# USB_CAN.net
KiCad netlist of a schematic drawn in Altium Designer
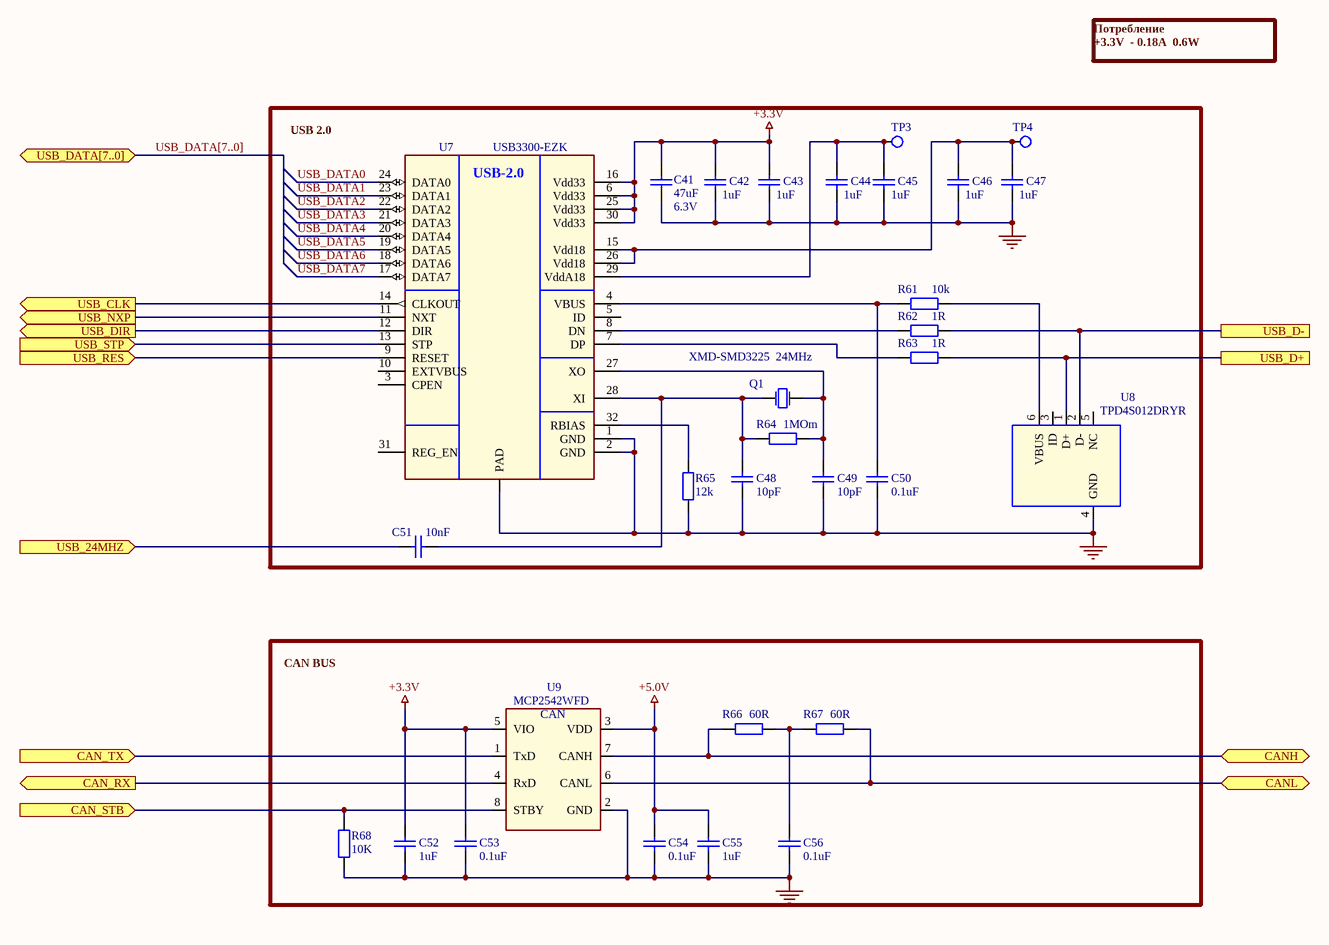
[diagram p0: USB_CAN.SchDoc]

(export (version "E")
  (design (tool "Eeschema 10.0.6"))
  (components
    (comp (ref "C41")
      (value "47uF")
      (footprint "C0805")
      (description "C0805C476M9PAC")
      (fields (field (name "VOLTAGE") "6.3V") (field (name "Comment") "Cap"))
      (libsource (lib "Terra") (part "Cap"))
    )
    (comp (ref "C42")
      (value "1uF")
      (footprint "C0603")
      (description "Конденсатор керамический")
      (fields (field (name "Comment") "Cap"))
      (libsource (lib "Terra") (part "Cap"))
    )
    (comp (ref "C43")
      (value "1uF")
      (footprint "C0603")
      (description "Конденсатор керамический")
      (fields (field (name "Comment") "Cap"))
      (libsource (lib "Terra") (part "Cap"))
    )
    (comp (ref "C44")
      (value "1uF")
      (footprint "C0603")
      (description "Конденсатор керамический")
      (fields (field (name "Comment") "Cap"))
      (libsource (lib "Terra") (part "Cap"))
    )
    (comp (ref "C45")
      (value "1uF")
      (footprint "C0603")
      (description "Конденсатор керамический")
      (fields (field (name "Comment") "Cap"))
      (libsource (lib "Terra") (part "Cap"))
    )
    (comp (ref "C46")
      (value "1uF")
      (footprint "C0603")
      (description "Конденсатор керамический")
      (fields (field (name "Comment") "Cap"))
      (libsource (lib "Terra") (part "Cap"))
    )
    (comp (ref "C47")
      (value "1uF")
      (footprint "C0603")
      (description "Конденсатор керамический")
      (fields (field (name "Comment") "Cap"))
      (libsource (lib "Terra") (part "Cap"))
    )
    (comp (ref "C48")
      (value "10pF")
      (footprint "C0402")
      (description "GRM1535C1H100J")
      (fields (field (name "Comment") "Cap"))
      (libsource (lib "Terra") (part "Cap"))
    )
    (comp (ref "C49")
      (value "10pF")
      (footprint "C0402")
      (description "GRM1535C1H100J")
      (fields (field (name "Comment") "Cap"))
      (libsource (lib "Terra") (part "Cap"))
    )
    (comp (ref "C50")
      (value "0.1uF")
      (footprint "C0402")
      (description "Конденсатор керамический")
      (fields (field (name "VOLTAGE") "25V") (field (name "Comment") "Cap"))
      (libsource (lib "Terra") (part "Cap"))
    )
    (comp (ref "C51")
      (value "10nF")
      (footprint "C0402")
      (description "Конденсатор керамический")
      (fields (field (name "VOLTAGE") "25V") (field (name "Comment") "Cap"))
      (libsource (lib "Terra") (part "Cap"))
    )
    (comp (ref "C52")
      (value "1uF")
      (footprint "C0603")
      (description "Конденсатор керамический")
      (fields (field (name "Comment") "Cap"))
      (libsource (lib "Terra") (part "Cap"))
    )
    (comp (ref "C53")
      (value "0.1uF")
      (footprint "C0402")
      (description "Конденсатор керамический")
      (fields (field (name "VOLTAGE") "25V") (field (name "Comment") "Cap"))
      (libsource (lib "Terra") (part "Cap"))
    )
    (comp (ref "C54")
      (value "0.1uF")
      (footprint "C0402")
      (description "Конденсатор керамический")
      (fields (field (name "VOLTAGE") "25V") (field (name "Comment") "Cap"))
      (libsource (lib "Terra") (part "Cap"))
    )
    (comp (ref "C55")
      (value "1uF")
      (footprint "C0603")
      (description "Конденсатор керамический")
      (fields (field (name "Comment") "Cap"))
      (libsource (lib "Terra") (part "Cap"))
    )
    (comp (ref "C56")
      (value "0.1uF")
      (footprint "C0402")
      (description "Конденсатор керамический")
      (fields (field (name "VOLTAGE") "25V") (field (name "Comment") "Cap"))
      (libsource (lib "Terra") (part "Cap"))
    )
    (comp (ref "Q1")
      (value "XMD-SMD3225  24MHz")
      (footprint "KX-5T")
      (description "Chengdu Kingbri Frequency Technology Co., Ltd   24MHz")
      (libsource (lib "common") (part "XTAL"))
    )
    (comp (ref "R61")
      (value "10k")
      (footprint "R0402")
      (description "Резистор")
      (fields (field (name "Comment") "Res2"))
      (libsource (lib "") (part "Res2_2"))
    )
    (comp (ref "R62")
      (value "1R")
      (footprint "R0402")
      (description "Резистор")
      (fields (field (name "Comment") "Res2"))
      (libsource (lib "Terra") (part "Res2"))
    )
    (comp (ref "R63")
      (value "1R")
      (footprint "R0402")
      (description "Резистор")
      (fields (field (name "Comment") "Res2"))
      (libsource (lib "Terra") (part "Res2"))
    )
    (comp (ref "R64")
      (value "1MOm")
      (footprint "R0402")
      (description "Резистор")
      (fields (field (name "Comment") "Res2"))
      (libsource (lib "") (part "Res2_2"))
    )
    (comp (ref "R65")
      (value "12k")
      (footprint "R0402")
      (description "Резистор")
      (fields (field (name "Comment") "Res2"))
      (libsource (lib "") (part "Res2_1"))
    )
    (comp (ref "R66")
      (value "60R")
      (footprint "R0402")
      (description "Резистор")
      (fields (field (name "Comment") "Res2"))
      (libsource (lib "Terra") (part "Res2"))
    )
    (comp (ref "R67")
      (value "60R")
      (footprint "R0402")
      (description "Резистор")
      (fields (field (name "Comment") "Res2"))
      (libsource (lib "Terra") (part "Res2"))
    )
    (comp (ref "R68")
      (value "10K")
      (footprint "R0402")
      (description "Резистор")
      (fields (field (name "Comment") "Res2"))
      (libsource (lib "") (part "Res2_1"))
    )
    (comp (ref "TP3")
      (value "~")
      (footprint "TP_0MM5_1MM0")
      (description "Тестовая точка на плате")
      (libsource (lib "*") (part "Test_Point"))
    )
    (comp (ref "TP4")
      (value "~")
      (footprint "TP_0MM5_1MM0")
      (description "Тестовая точка на плате")
      (libsource (lib "*") (part "Test_Point"))
    )
    (comp (ref "U7")
      (value "USB3300-EZK")
      (footprint "QFN-32")
      (description "USB-2.0 driver")
      (libsource (lib "Terra") (part "USB3300"))
    )
    (comp (ref "U8")
      (value "TPD4S012DRYR")
      (footprint "TPD4S012DRYR")
      (description "Защитные диоды USB")
      (libsource (lib "common") (part "TPD4S012DRYR"))
    )
    (comp (ref "U9")
      (value "MCP2542WFD")
      (footprint "SO8")
      (description "CAN Transceiver")
      (libsource (lib "common") (part "MCP2542"))
    )
  )
  (nets
    (net (code "1") (name "+3.3V") (class "Default")
      (node (ref "C41") (pin "1") (pinfunction "1_1") (pintype "passive"))
      (node (ref "C42") (pin "2") (pinfunction "2_2") (pintype "passive"))
      (node (ref "C43") (pin "2") (pinfunction "2_2") (pintype "passive"))
      (node (ref "C52") (pin "1") (pinfunction "1_1") (pintype "passive"))
      (node (ref "C53") (pin "1") (pinfunction "1_1") (pintype "passive"))
      (node (ref "U7") (pin "16") (pinfunction "Vdd33_16") (pintype "power_in"))
      (node (ref "U7") (pin "25") (pinfunction "Vdd33_25") (pintype "power_in"))
      (node (ref "U7") (pin "30") (pinfunction "Vdd33_30") (pintype "power_in"))
      (node (ref "U7") (pin "6") (pinfunction "Vdd33_6") (pintype "power_in"))
      (node (ref "U9") (pin "5") (pinfunction "VIO_5") (pintype "passive"))
    )
    (net (code "2") (name "+5.0V") (class "Default")
      (node (ref "C54") (pin "1") (pinfunction "1_1") (pintype "passive"))
      (node (ref "C55") (pin "1") (pinfunction "1_1") (pintype "passive"))
      (node (ref "U9") (pin "3") (pinfunction "VDD_3") (pintype "power_in"))
    )
    (net (code "3") (name "/CANH") (class "Default")
      (node (ref "R66") (pin "2") (pinfunction "2_2") (pintype "passive"))
      (node (ref "U9") (pin "7") (pinfunction "CANH_7") (pintype "passive"))
    )
    (net (code "4") (name "/CANL") (class "Default")
      (node (ref "R67") (pin "1") (pinfunction "1_1") (pintype "passive"))
      (node (ref "U9") (pin "6") (pinfunction "CANL_6") (pintype "passive"))
    )
    (net (code "5") (name "/CAN_RX") (class "Default")
      (node (ref "U9") (pin "4") (pinfunction "RxD_4") (pintype "passive"))
    )
    (net (code "6") (name "/CAN_STB") (class "Default")
      (node (ref "R68") (pin "1") (pinfunction "1_1") (pintype "passive"))
      (node (ref "U9") (pin "8") (pinfunction "STBY_8") (pintype "passive"))
    )
    (net (code "7") (name "/CAN_TX") (class "Default")
      (node (ref "U9") (pin "1") (pinfunction "TxD_1") (pintype "passive"))
    )
    (net (code "8") (name "/USB_24MHZ") (class "Default")
      (node (ref "C51") (pin "1") (pinfunction "1_1") (pintype "passive"))
    )
    (net (code "9") (name "/USB_CLK") (class "Default")
      (node (ref "U7") (pin "14") (pinfunction "CLKOUT_14") (pintype "output"))
    )
    (net (code "10") (name "/USB_D+") (class "Default")
      (node (ref "R63") (pin "1") (pinfunction "1_1") (pintype "passive"))
      (node (ref "U8") (pin "1") (pinfunction "D+_1") (pintype "passive"))
    )
    (net (code "11") (name "/USB_D-") (class "Default")
      (node (ref "R62") (pin "1") (pinfunction "1_1") (pintype "passive"))
      (node (ref "U8") (pin "2") (pinfunction "D-_2") (pintype "passive"))
    )
    (net (code "12") (name "/USB_DATA0") (class "Default")
      (node (ref "U7") (pin "24") (pinfunction "DATA0_24") (pintype "bidirectional"))
    )
    (net (code "13") (name "/USB_DATA1") (class "Default")
      (node (ref "U7") (pin "23") (pinfunction "DATA1_23") (pintype "bidirectional"))
    )
    (net (code "14") (name "/USB_DATA2") (class "Default")
      (node (ref "U7") (pin "22") (pinfunction "DATA2_22") (pintype "bidirectional"))
    )
    (net (code "15") (name "/USB_DATA3") (class "Default")
      (node (ref "U7") (pin "21") (pinfunction "DATA3_21") (pintype "bidirectional"))
    )
    (net (code "16") (name "/USB_DATA4") (class "Default")
      (node (ref "U7") (pin "20") (pinfunction "DATA4_20") (pintype "bidirectional"))
    )
    (net (code "17") (name "/USB_DATA5") (class "Default")
      (node (ref "U7") (pin "19") (pinfunction "DATA5_19") (pintype "bidirectional"))
    )
    (net (code "18") (name "/USB_DATA6") (class "Default")
      (node (ref "U7") (pin "18") (pinfunction "DATA6_18") (pintype "bidirectional"))
    )
    (net (code "19") (name "/USB_DATA7") (class "Default")
      (node (ref "U7") (pin "17") (pinfunction "DATA7_17") (pintype "bidirectional"))
    )
    (net (code "21") (name "/USB_DIR") (class "Default")
      (node (ref "U7") (pin "12") (pinfunction "DIR_12") (pintype "passive"))
    )
    (net (code "22") (name "/USB_NXP") (class "Default")
      (node (ref "U7") (pin "11") (pinfunction "NXT_11") (pintype "passive"))
    )
    (net (code "23") (name "/USB_RES") (class "Default")
      (node (ref "U7") (pin "9") (pinfunction "RESET_9") (pintype "passive"))
    )
    (net (code "24") (name "/USB_STP") (class "Default")
      (node (ref "U7") (pin "13") (pinfunction "STP_13") (pintype "passive"))
    )
    (net (code "25") (name "GND") (class "Default")
      (node (ref "C41") (pin "2") (pinfunction "2_2") (pintype "passive"))
      (node (ref "C42") (pin "1") (pinfunction "1_1") (pintype "passive"))
      (node (ref "C43") (pin "1") (pinfunction "1_1") (pintype "passive"))
      (node (ref "C44") (pin "1") (pinfunction "1_1") (pintype "passive"))
      (node (ref "C45") (pin "1") (pinfunction "1_1") (pintype "passive"))
      (node (ref "C46") (pin "1") (pinfunction "1_1") (pintype "passive"))
      (node (ref "C47") (pin "1") (pinfunction "1_1") (pintype "passive"))
      (node (ref "C48") (pin "2") (pinfunction "2_2") (pintype "passive"))
      (node (ref "C49") (pin "2") (pinfunction "2_2") (pintype "passive"))
      (node (ref "C50") (pin "2") (pinfunction "2_2") (pintype "passive"))
      (node (ref "C52") (pin "2") (pinfunction "2_2") (pintype "passive"))
      (node (ref "C53") (pin "2") (pinfunction "2_2") (pintype "passive"))
      (node (ref "C54") (pin "2") (pinfunction "2_2") (pintype "passive"))
      (node (ref "C55") (pin "2") (pinfunction "2_2") (pintype "passive"))
      (node (ref "C56") (pin "2") (pinfunction "2_2") (pintype "passive"))
      (node (ref "R65") (pin "2") (pinfunction "2_2") (pintype "passive"))
      (node (ref "R68") (pin "2") (pinfunction "2_2") (pintype "passive"))
      (node (ref "U7") (pin "0") (pinfunction "PAD_0") (pintype "passive"))
      (node (ref "U7") (pin "1") (pinfunction "GND_1") (pintype "power_in"))
      (node (ref "U7") (pin "2") (pinfunction "GND_2") (pintype "power_in"))
      (node (ref "U8") (pin "4") (pinfunction "GND_4") (pintype "passive"))
      (node (ref "U9") (pin "2") (pinfunction "GND_2") (pintype "power_in"))
    )
    (net (code "26") (name "Net-(C56-Pad1)") (class "Default")
      (node (ref "C56") (pin "1") (pinfunction "1_1") (pintype "passive"))
      (node (ref "R66") (pin "1") (pinfunction "1_1") (pintype "passive"))
      (node (ref "R67") (pin "2") (pinfunction "2_2") (pintype "passive"))
    )
    (net (code "27") (name "Net-(Q1-OSC1)") (class "Default")
      (node (ref "C48") (pin "1") (pinfunction "1_1") (pintype "passive"))
      (node (ref "C51") (pin "2") (pinfunction "2_2") (pintype "passive"))
      (node (ref "Q1") (pin "1") (pinfunction "OSC1_1") (pintype "passive"))
      (node (ref "R64") (pin "1") (pinfunction "1_1") (pintype "passive"))
      (node (ref "U7") (pin "28") (pinfunction "XI_28") (pintype "passive"))
    )
    (net (code "28") (name "Net-(Q1-OSC2)") (class "Default")
      (node (ref "C49") (pin "1") (pinfunction "1_1") (pintype "passive"))
      (node (ref "Q1") (pin "3") (pinfunction "OSC2_3") (pintype "passive"))
      (node (ref "R64") (pin "2") (pinfunction "2_2") (pintype "passive"))
      (node (ref "U7") (pin "27") (pinfunction "XO_27") (pintype "passive"))
    )
    (net (code "29") (name "Net-(TP3-e1)") (class "Default")
      (node (ref "C44") (pin "2") (pinfunction "2_2") (pintype "passive"))
      (node (ref "C45") (pin "2") (pinfunction "2_2") (pintype "passive"))
      (node (ref "TP3") (pin "1") (pinfunction "e1_1") (pintype "passive"))
      (node (ref "U7") (pin "29") (pinfunction "VddA18_29") (pintype "power_in"))
    )
    (net (code "30") (name "Net-(TP4-e1)") (class "Default")
      (node (ref "C46") (pin "2") (pinfunction "2_2") (pintype "passive"))
      (node (ref "C47") (pin "2") (pinfunction "2_2") (pintype "passive"))
      (node (ref "TP4") (pin "1") (pinfunction "e1_1") (pintype "passive"))
      (node (ref "U7") (pin "15") (pinfunction "Vdd18_15") (pintype "power_in"))
      (node (ref "U7") (pin "26") (pinfunction "Vdd18_26") (pintype "power_in"))
    )
    (net (code "31") (name "Net-(U7-DN)") (class "Default")
      (node (ref "R62") (pin "2") (pinfunction "2_2") (pintype "passive"))
      (node (ref "U7") (pin "8") (pinfunction "DN_8") (pintype "passive"))
    )
    (net (code "32") (name "Net-(U7-DP)") (class "Default")
      (node (ref "R63") (pin "2") (pinfunction "2_2") (pintype "passive"))
      (node (ref "U7") (pin "7") (pinfunction "DP_7") (pintype "passive"))
    )
    (net (code "33") (name "Net-(U7-RBIAS)") (class "Default")
      (node (ref "R65") (pin "1") (pinfunction "1_1") (pintype "passive"))
      (node (ref "U7") (pin "32") (pinfunction "RBIAS_32") (pintype "passive"))
    )
    (net (code "34") (name "Net-(U7-VBUS)") (class "Default")
      (node (ref "C50") (pin "1") (pinfunction "1_1") (pintype "passive"))
      (node (ref "R61") (pin "1") (pinfunction "1_1") (pintype "passive"))
      (node (ref "U7") (pin "4") (pinfunction "VBUS_4") (pintype "passive"))
    )
    (net (code "35") (name "Net-(U8-VBUS)") (class "Default")
      (node (ref "R61") (pin "2") (pinfunction "2_2") (pintype "passive"))
      (node (ref "U8") (pin "6") (pinfunction "VBUS_6") (pintype "passive"))
    )
    (net (code "36") (name "unconnected-(U7-CPEN-Pad3)") (class "Default")
      (node (ref "U7") (pin "3") (pinfunction "CPEN_3") (pintype "passive"))
    )
    (net (code "37") (name "unconnected-(U7-EXTVBUS-Pad10)") (class "Default")
      (node (ref "U7") (pin "10") (pinfunction "EXTVBUS_10") (pintype "passive"))
    )
    (net (code "38") (name "unconnected-(U7-ID-Pad5)") (class "Default")
      (node (ref "U7") (pin "5") (pinfunction "ID_5") (pintype "passive"))
    )
    (net (code "39") (name "unconnected-(U7-REG_EN-Pad31)") (class "Default")
      (node (ref "U7") (pin "31") (pinfunction "REG_EN_31") (pintype "passive"))
    )
    (net (code "40") (name "unconnected-(U8-ID-Pad3)") (class "Default")
      (node (ref "U8") (pin "3") (pinfunction "ID_3") (pintype "passive"))
    )
    (net (code "41") (name "unconnected-(U8-NC-Pad5)") (class "Default")
      (node (ref "U8") (pin "5") (pinfunction "NC_5") (pintype "passive"))
    )
    (net (code "42") (name "unconnected-(U9-NC-Pad4)") (class "Default")
      (node (ref "U9") (pin "4") (pinfunction "NC_4") (pintype "passive"))
    )
    (net (code "43") (name "unconnected-(U9-NC-Pad5)") (class "Default")
      (node (ref "U9") (pin "5") (pinfunction "NC_5") (pintype "passive"))
    )
  )
)
